# BBB_Connections.net
KiCad netlist of a schematic drawn in Altium Designer
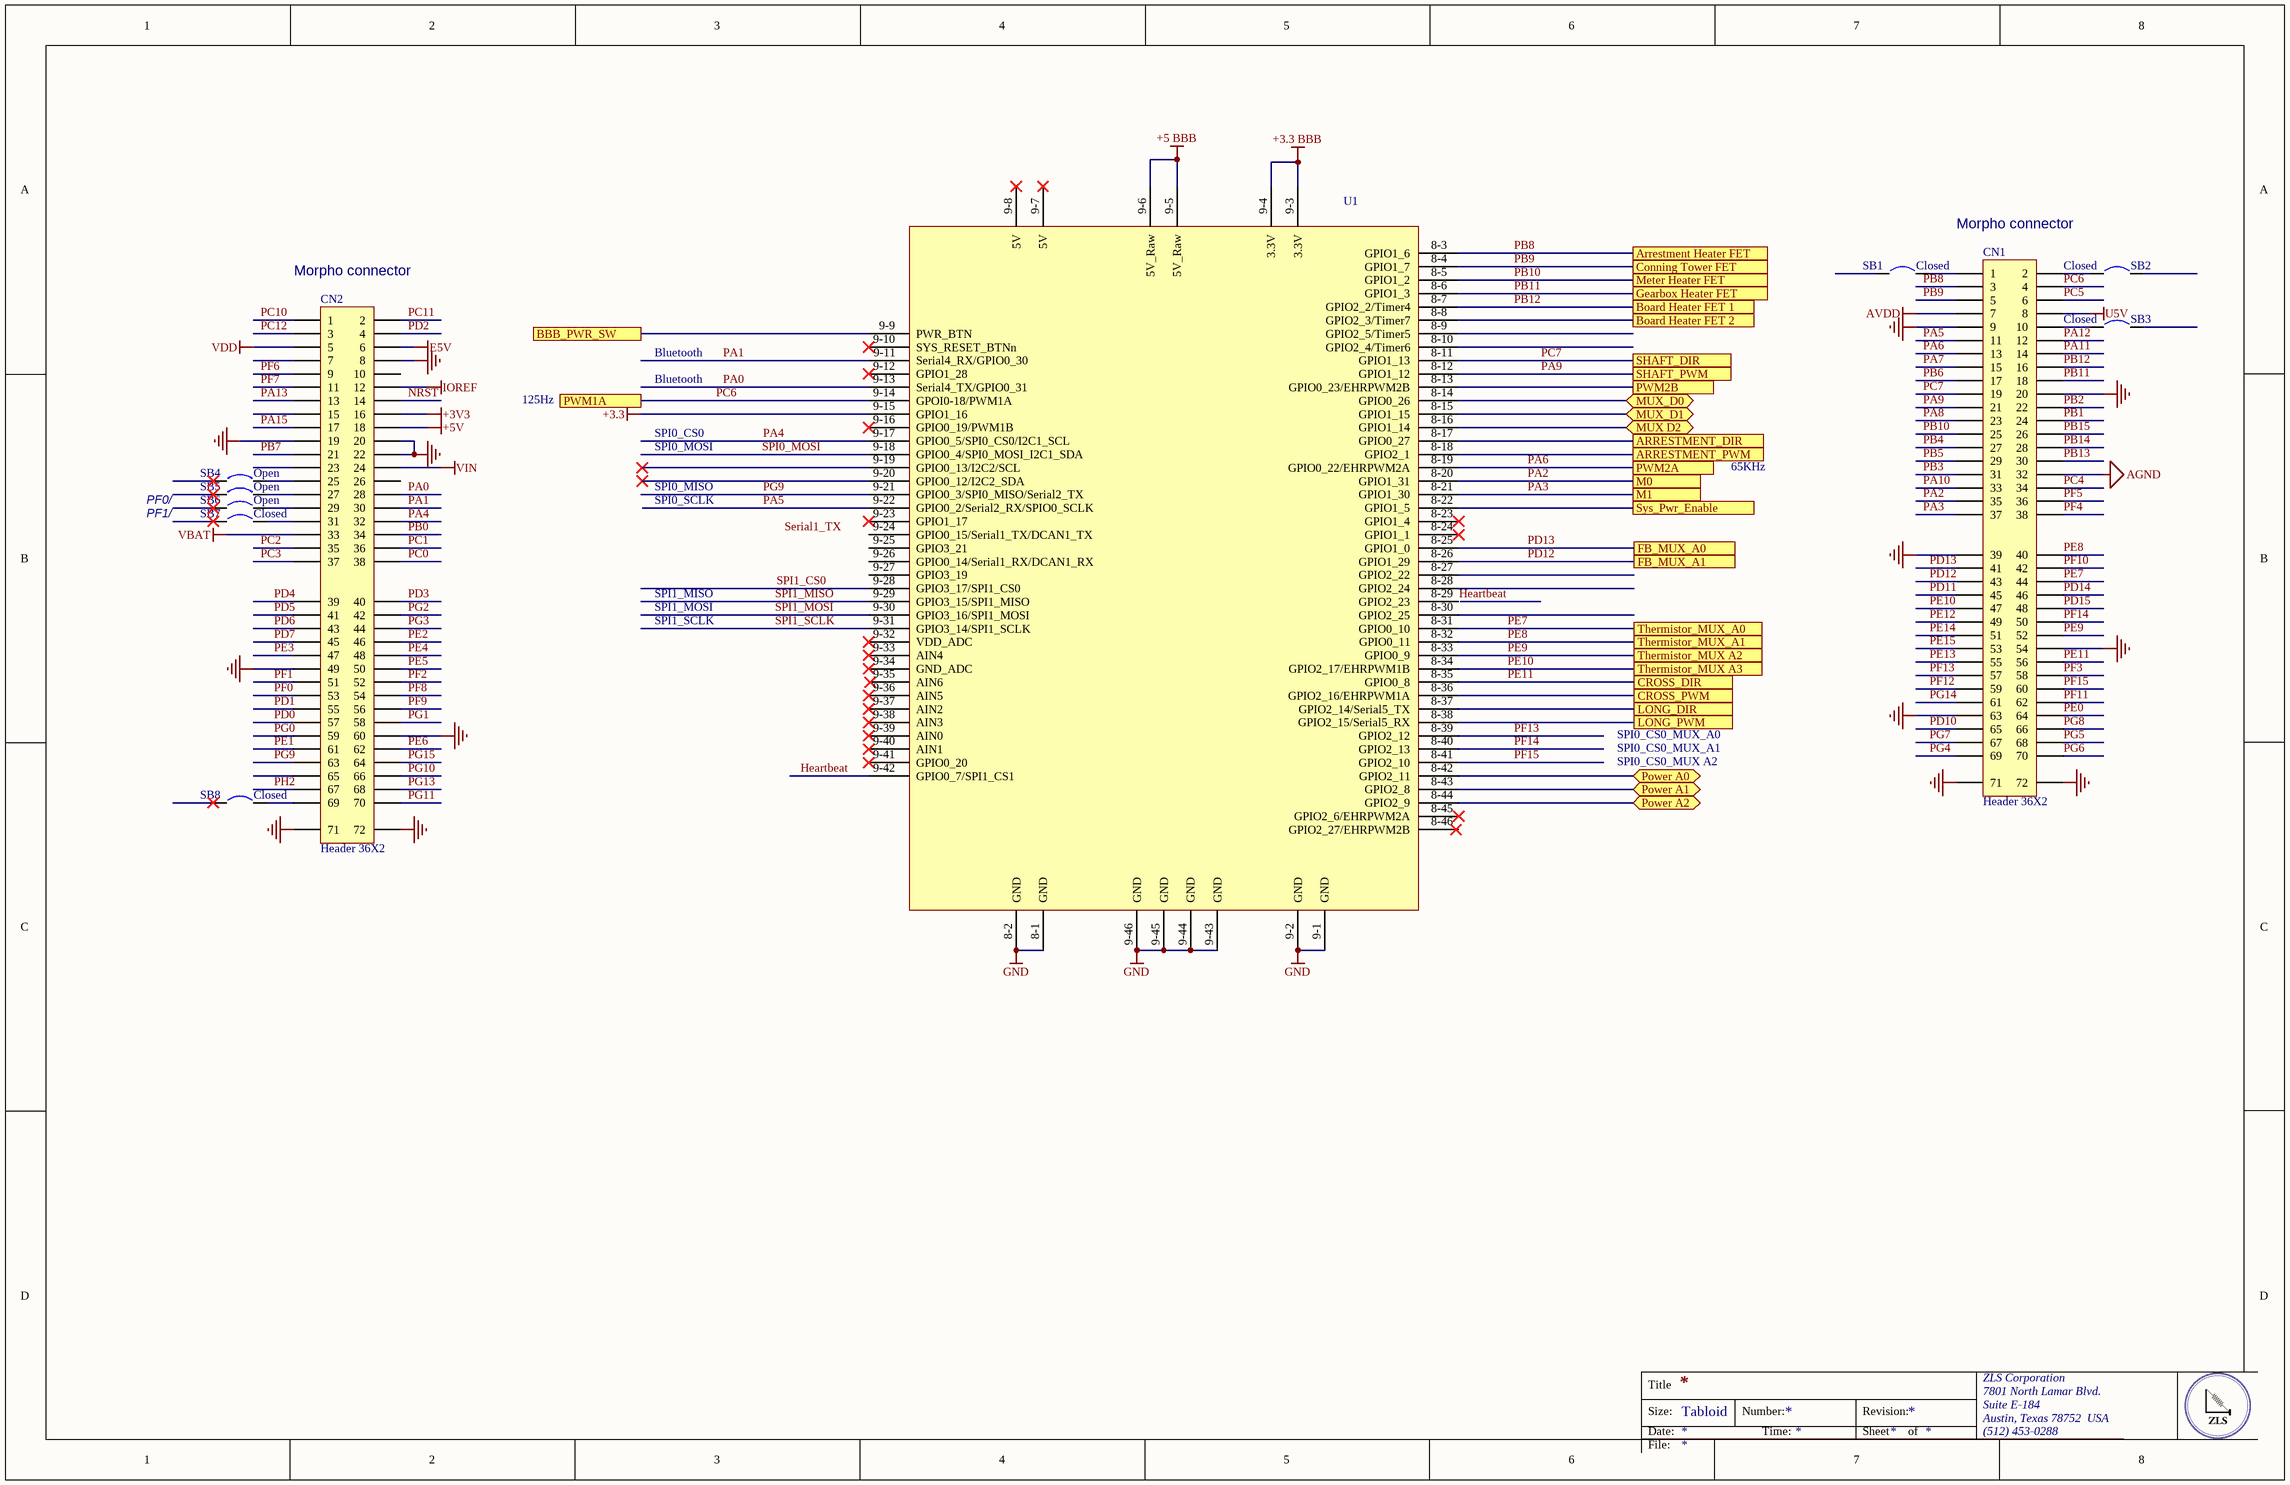
[diagram p0: BBB_Connections.SchDoc]

(export (version "E")
  (design (tool "Eeschema 10.0.6"))
  (components
    (comp (ref "CN1")
      (value "Header 36X2")
      (footprint "HDR_2x36_2R54_V_M")
      (description "Header, 36-Pin, Dual row")
      (fields (field (name "PUBLISHER") "Altium Limited"))
      (libsource (lib "MB1137") (part "Header 36X2"))
    )
    (comp (ref "CN2")
      (value "Header 36X2")
      (footprint "HDR_2x36_2R54_V_M")
      (description "Header, 36-Pin, Dual row")
      (fields (field (name "PUBLISHER") "Altium Limited"))
      (libsource (lib "MB1137") (part "Header 36X2"))
    )
    (comp (ref "SB1")
      (value "Closed")
      (footprint "SB_0603")
      (description "Circuit Breaker")
      (fields (field (name "PUBLISHER") "Altium Limited"))
      (libsource (lib "MB1167") (part "Circuit Breaker_close"))
    )
    (comp (ref "SB2")
      (value "Closed")
      (footprint "SB_0603")
      (description "Circuit Breaker")
      (fields (field (name "PUBLISHER") "Altium Limited"))
      (libsource (lib "") (part "Circuit Breaker_close_1"))
    )
    (comp (ref "SB3")
      (value "Closed")
      (footprint "SB_0603")
      (description "Circuit Breaker")
      (fields (field (name "PUBLISHER") "Altium Limited"))
      (libsource (lib "MB1167") (part "Circuit Breaker_close"))
    )
    (comp (ref "SB4")
      (value "Open")
      (footprint "SB_0603")
      (description "Circuit Breaker")
      (fields (field (name "PUBLISHER") "Altium Limited"))
      (libsource (lib "MB1167") (part "Circuit Breaker"))
    )
    (comp (ref "SB5")
      (value "Open")
      (footprint "SB_0603")
      (description "Circuit Breaker")
      (fields (field (name "PUBLISHER") "Altium Limited"))
      (libsource (lib "MB1167") (part "Circuit Breaker"))
    )
    (comp (ref "SB6")
      (value "Open")
      (footprint "SB_0603")
      (description "Circuit Breaker")
      (fields (field (name "PUBLISHER") "Altium Limited"))
      (libsource (lib "MB1167") (part "Circuit Breaker"))
    )
    (comp (ref "SB7")
      (value "Closed")
      (footprint "SB_0603")
      (description "Circuit Breaker")
      (fields (field (name "PUBLISHER") "Altium Limited"))
      (libsource (lib "MB1167") (part "Circuit Breaker_close"))
    )
    (comp (ref "SB8")
      (value "Closed")
      (footprint "SB_0603")
      (description "Circuit Breaker")
      (fields (field (name "PUBLISHER") "Altium Limited"))
      (libsource (lib "MB1167") (part "Circuit Breaker_close"))
    )
    (comp (ref "U1")
      (value "BBB Header x 2")
      (footprint "Beaglebone Black Thru")
      (description "Beaglebone Black Header")
      (fields
        (field (name "MANUFACTURER") "Samtec Inc.")
        (field (name "MANUFACTURER PART NUMBER") "SSW-123-03-G-D")
      )
      (libsource (lib "ZLS_Schematic_lib") (part "Beaglebone_Black"))
    )
  )
  (nets
    (net (code "1") (name "+3.3") (class "Default")
      (node (ref "U1") (pin "9-15") (pinfunction "GPIO1_16_9-15") (pintype "passive"))
    )
    (net (code "2") (name "+3.3 BBB") (class "Default")
      (node (ref "U1") (pin "9-3") (pinfunction "3.3V_9-3") (pintype "passive"))
      (node (ref "U1") (pin "9-4") (pinfunction "3.3V_9-4") (pintype "passive"))
    )
    (net (code "3") (name "+3V3") (class "Default")
      (node (ref "CN2") (pin "16") (pinfunction "16_16") (pintype "passive"))
    )
    (net (code "4") (name "+5 BBB") (class "Default")
      (node (ref "U1") (pin "9-5") (pinfunction "5V_Raw_9-5") (pintype "passive"))
      (node (ref "U1") (pin "9-6") (pinfunction "5V_Raw_9-6") (pintype "passive"))
    )
    (net (code "5") (name "+5V") (class "Default")
      (node (ref "CN2") (pin "18") (pinfunction "18_18") (pintype "passive"))
    )
    (net (code "6") (name "/ARRESTMENT_DIR") (class "Default")
      (node (ref "U1") (pin "8-17") (pinfunction "GPIO0_27_8-17") (pintype "passive"))
    )
    (net (code "7") (name "/ARRESTMENT_PWM") (class "Default")
      (node (ref "U1") (pin "8-18") (pinfunction "GPIO2_1_8-18") (pintype "passive"))
    )
    (net (code "8") (name "/BBB_PWR_SW") (class "Default")
      (node (ref "U1") (pin "9-9") (pinfunction "PWR_BTN_9-9") (pintype "passive"))
    )
    (net (code "9") (name "/Board Heater FET 2") (class "Default")
      (node (ref "U1") (pin "8-8") (pinfunction "GPIO2_3/Timer7_8-8") (pintype "passive"))
    )
    (net (code "10") (name "/CROSS_PWM") (class "Default")
      (node (ref "U1") (pin "8-36") (pinfunction "GPIO2_16/EHRPWM1A_8-36") (pintype "passive"))
    )
    (net (code "11") (name "/Heartbeat") (class "Default")
      (node (ref "U1") (pin "8-29") (pinfunction "GPIO2_23_8-29") (pintype "passive"))
      (node (ref "U1") (pin "9-42") (pinfunction "GPIO0_7/SPI1_CS1_9-42") (pintype "passive"))
    )
    (net (code "12") (name "/LONG_DIR") (class "Default")
      (node (ref "U1") (pin "8-37") (pinfunction "GPIO2_14/Serial5_TX_8-37") (pintype "passive"))
    )
    (net (code "13") (name "/LONG_PWM") (class "Default")
      (node (ref "U1") (pin "8-38") (pinfunction "GPIO2_15/Serial5_RX_8-38") (pintype "passive"))
    )
    (net (code "14") (name "/MUX D2") (class "Default")
      (node (ref "U1") (pin "8-16") (pinfunction "GPIO1_14_8-16") (pintype "passive"))
    )
    (net (code "15") (name "/MUX_D0") (class "Default")
      (node (ref "U1") (pin "8-14") (pinfunction "GPIO0_26_8-14") (pintype "passive"))
    )
    (net (code "16") (name "/MUX_D1") (class "Default")
      (node (ref "U1") (pin "8-15") (pinfunction "GPIO1_15_8-15") (pintype "passive"))
    )
    (net (code "17") (name "/NRST") (class "Default")
      (node (ref "CN2") (pin "14") (pinfunction "14_14") (pintype "passive"))
    )
    (net (code "18") (name "/PA0") (class "Default")
      (node (ref "CN2") (pin "28") (pinfunction "28_28") (pintype "passive"))
      (node (ref "U1") (pin "9-13") (pinfunction "Serial4_TX/GPIO0_31_9-13") (pintype "passive"))
    )
    (net (code "19") (name "/PA1") (class "Default")
      (node (ref "CN2") (pin "30") (pinfunction "30_30") (pintype "passive"))
      (node (ref "U1") (pin "9-11") (pinfunction "Serial4_RX/GPIO0_30_9-11") (pintype "passive"))
    )
    (net (code "20") (name "/PA2") (class "Default")
      (node (ref "CN1") (pin "35") (pinfunction "35_35") (pintype "passive"))
      (node (ref "U1") (pin "8-20") (pinfunction "GPIO1_31_8-20") (pintype "passive"))
    )
    (net (code "21") (name "/PA3") (class "Default")
      (node (ref "CN1") (pin "37") (pinfunction "37_37") (pintype "passive"))
      (node (ref "U1") (pin "8-21") (pinfunction "GPIO1_30_8-21") (pintype "passive"))
    )
    (net (code "22") (name "/PA4") (class "Default")
      (node (ref "CN2") (pin "32") (pinfunction "32_32") (pintype "passive"))
      (node (ref "U1") (pin "9-17") (pinfunction "GPIO0_5/SPI0_CS0/I2C1_SCL_9-17") (pintype "passive"))
    )
    (net (code "23") (name "/PA5") (class "Default")
      (node (ref "CN1") (pin "11") (pinfunction "11_11") (pintype "passive"))
      (node (ref "U1") (pin "9-22") (pinfunction "GPIO0_2/Serial2_RX/SPIO0_SCLK_9-22") (pintype "passive"))
    )
    (net (code "24") (name "/PA6") (class "Default")
      (node (ref "CN1") (pin "13") (pinfunction "13_13") (pintype "passive"))
      (node (ref "U1") (pin "8-19") (pinfunction "GPIO0_22/EHRPWM2A_8-19") (pintype "passive"))
    )
    (net (code "25") (name "/PA7") (class "Default")
      (node (ref "CN1") (pin "15") (pinfunction "15_15") (pintype "passive"))
    )
    (net (code "26") (name "/PA8") (class "Default")
      (node (ref "CN1") (pin "23") (pinfunction "23_23") (pintype "passive"))
    )
    (net (code "27") (name "/PA9") (class "Default")
      (node (ref "CN1") (pin "21") (pinfunction "21_21") (pintype "passive"))
      (node (ref "U1") (pin "8-12") (pinfunction "GPIO1_12_8-12") (pintype "passive"))
    )
    (net (code "28") (name "/PA10") (class "Default")
      (node (ref "CN1") (pin "33") (pinfunction "33_33") (pintype "passive"))
    )
    (net (code "29") (name "/PA11") (class "Default")
      (node (ref "CN1") (pin "14") (pinfunction "14_14") (pintype "passive"))
    )
    (net (code "30") (name "/PA12") (class "Default")
      (node (ref "CN1") (pin "12") (pinfunction "12_12") (pintype "passive"))
    )
    (net (code "31") (name "/PA13") (class "Default")
      (node (ref "CN2") (pin "13") (pinfunction "13_13") (pintype "passive"))
    )
    (net (code "32") (name "/PA15") (class "Default")
      (node (ref "CN2") (pin "17") (pinfunction "17_17") (pintype "passive"))
    )
    (net (code "33") (name "/PB0") (class "Default")
      (node (ref "CN2") (pin "34") (pinfunction "34_34") (pintype "passive"))
    )
    (net (code "34") (name "/PB1") (class "Default")
      (node (ref "CN1") (pin "24") (pinfunction "24_24") (pintype "passive"))
    )
    (net (code "35") (name "/PB2") (class "Default")
      (node (ref "CN1") (pin "22") (pinfunction "22_22") (pintype "passive"))
    )
    (net (code "36") (name "/PB3") (class "Default")
      (node (ref "CN1") (pin "31") (pinfunction "31_31") (pintype "passive"))
    )
    (net (code "37") (name "/PB4") (class "Default")
      (node (ref "CN1") (pin "27") (pinfunction "27_27") (pintype "passive"))
    )
    (net (code "38") (name "/PB5") (class "Default")
      (node (ref "CN1") (pin "29") (pinfunction "29_29") (pintype "passive"))
    )
    (net (code "39") (name "/PB6") (class "Default")
      (node (ref "CN1") (pin "17") (pinfunction "17_17") (pintype "passive"))
    )
    (net (code "40") (name "/PB7") (class "Default")
      (node (ref "CN2") (pin "21") (pinfunction "21_21") (pintype "passive"))
    )
    (net (code "41") (name "/PB8") (class "Default")
      (node (ref "CN1") (pin "3") (pinfunction "3_3") (pintype "passive"))
      (node (ref "U1") (pin "8-3") (pinfunction "GPIO1_6_8-3") (pintype "passive"))
    )
    (net (code "42") (name "/PB9") (class "Default")
      (node (ref "CN1") (pin "5") (pinfunction "5_5") (pintype "passive"))
      (node (ref "U1") (pin "8-4") (pinfunction "GPIO1_7_8-4") (pintype "passive"))
    )
    (net (code "43") (name "/PB10") (class "Default")
      (node (ref "CN1") (pin "25") (pinfunction "25_25") (pintype "passive"))
      (node (ref "U1") (pin "8-5") (pinfunction "GPIO1_2_8-5") (pintype "passive"))
    )
    (net (code "44") (name "/PB11") (class "Default")
      (node (ref "CN1") (pin "18") (pinfunction "18_18") (pintype "passive"))
      (node (ref "U1") (pin "8-6") (pinfunction "GPIO1_3_8-6") (pintype "passive"))
    )
    (net (code "45") (name "/PB12") (class "Default")
      (node (ref "CN1") (pin "16") (pinfunction "16_16") (pintype "passive"))
      (node (ref "U1") (pin "8-7") (pinfunction "GPIO2_2/Timer4_8-7") (pintype "passive"))
    )
    (net (code "46") (name "/PB13") (class "Default")
      (node (ref "CN1") (pin "30") (pinfunction "30_30") (pintype "passive"))
    )
    (net (code "47") (name "/PB14") (class "Default")
      (node (ref "CN1") (pin "28") (pinfunction "28_28") (pintype "passive"))
    )
    (net (code "48") (name "/PB15") (class "Default")
      (node (ref "CN1") (pin "26") (pinfunction "26_26") (pintype "passive"))
    )
    (net (code "49") (name "/PC0") (class "Default")
      (node (ref "CN2") (pin "38") (pinfunction "38_38") (pintype "passive"))
    )
    (net (code "50") (name "/PC1") (class "Default")
      (node (ref "CN2") (pin "36") (pinfunction "36_36") (pintype "passive"))
    )
    (net (code "51") (name "/PC2") (class "Default")
      (node (ref "CN2") (pin "35") (pinfunction "35_35") (pintype "passive"))
    )
    (net (code "52") (name "/PC3") (class "Default")
      (node (ref "CN2") (pin "37") (pinfunction "37_37") (pintype "passive"))
    )
    (net (code "53") (name "/PC4") (class "Default")
      (node (ref "CN1") (pin "34") (pinfunction "34_34") (pintype "passive"))
    )
    (net (code "54") (name "/PC5") (class "Default")
      (node (ref "CN1") (pin "6") (pinfunction "6_6") (pintype "passive"))
    )
    (net (code "55") (name "/PC6") (class "Default")
      (node (ref "CN1") (pin "4") (pinfunction "4_4") (pintype "passive"))
      (node (ref "U1") (pin "9-14") (pinfunction "GPOI0-18/PWM1A_9-14") (pintype "passive"))
    )
    (net (code "56") (name "/PC7") (class "Default")
      (node (ref "CN1") (pin "19") (pinfunction "19_19") (pintype "passive"))
      (node (ref "U1") (pin "8-11") (pinfunction "GPIO1_13_8-11") (pintype "passive"))
    )
    (net (code "57") (name "/PC10") (class "Default")
      (node (ref "CN2") (pin "1") (pinfunction "1_1") (pintype "passive"))
    )
    (net (code "58") (name "/PC11") (class "Default")
      (node (ref "CN2") (pin "2") (pinfunction "2_2") (pintype "passive"))
    )
    (net (code "59") (name "/PC12") (class "Default")
      (node (ref "CN2") (pin "3") (pinfunction "3_3") (pintype "passive"))
    )
    (net (code "60") (name "/PD0") (class "Default")
      (node (ref "CN2") (pin "57") (pinfunction "57_57") (pintype "passive"))
    )
    (net (code "61") (name "/PD1") (class "Default")
      (node (ref "CN2") (pin "55") (pinfunction "55_55") (pintype "passive"))
    )
    (net (code "62") (name "/PD2") (class "Default")
      (node (ref "CN2") (pin "4") (pinfunction "4_4") (pintype "passive"))
    )
    (net (code "63") (name "/PD3") (class "Default")
      (node (ref "CN2") (pin "40") (pinfunction "40_40") (pintype "passive"))
    )
    (net (code "64") (name "/PD4") (class "Default")
      (node (ref "CN2") (pin "39") (pinfunction "39_39") (pintype "passive"))
    )
    (net (code "65") (name "/PD5") (class "Default")
      (node (ref "CN2") (pin "41") (pinfunction "41_41") (pintype "passive"))
    )
    (net (code "66") (name "/PD6") (class "Default")
      (node (ref "CN2") (pin "43") (pinfunction "43_43") (pintype "passive"))
    )
    (net (code "67") (name "/PD7") (class "Default")
      (node (ref "CN2") (pin "45") (pinfunction "45_45") (pintype "passive"))
    )
    (net (code "68") (name "/PD10") (class "Default")
      (node (ref "CN1") (pin "65") (pinfunction "65_65") (pintype "passive"))
    )
    (net (code "69") (name "/PD11") (class "Default")
      (node (ref "CN1") (pin "45") (pinfunction "45_45") (pintype "passive"))
    )
    (net (code "70") (name "/PD12") (class "Default")
      (node (ref "CN1") (pin "43") (pinfunction "43_43") (pintype "passive"))
      (node (ref "U1") (pin "8-26") (pinfunction "GPIO1_29_8-26") (pintype "passive"))
    )
    (net (code "71") (name "/PD13") (class "Default")
      (node (ref "CN1") (pin "41") (pinfunction "41_41") (pintype "passive"))
      (node (ref "U1") (pin "8-25") (pinfunction "GPIO1_0_8-25") (pintype "passive"))
    )
    (net (code "72") (name "/PD14") (class "Default")
      (node (ref "CN1") (pin "46") (pinfunction "46_46") (pintype "passive"))
    )
    (net (code "73") (name "/PD15") (class "Default")
      (node (ref "CN1") (pin "48") (pinfunction "48_48") (pintype "passive"))
    )
    (net (code "74") (name "/PE0") (class "Default")
      (node (ref "CN1") (pin "64") (pinfunction "64_64") (pintype "passive"))
    )
    (net (code "75") (name "/PE1") (class "Default")
      (node (ref "CN2") (pin "61") (pinfunction "61_61") (pintype "passive"))
    )
    (net (code "76") (name "/PE2") (class "Default")
      (node (ref "CN2") (pin "46") (pinfunction "46_46") (pintype "passive"))
    )
    (net (code "77") (name "/PE3") (class "Default")
      (node (ref "CN2") (pin "47") (pinfunction "47_47") (pintype "passive"))
    )
    (net (code "78") (name "/PE4") (class "Default")
      (node (ref "CN2") (pin "48") (pinfunction "48_48") (pintype "passive"))
    )
    (net (code "79") (name "/PE5") (class "Default")
      (node (ref "CN2") (pin "50") (pinfunction "50_50") (pintype "passive"))
    )
    (net (code "80") (name "/PE6") (class "Default")
      (node (ref "CN2") (pin "62") (pinfunction "62_62") (pintype "passive"))
    )
    (net (code "81") (name "/PE7") (class "Default")
      (node (ref "CN1") (pin "44") (pinfunction "44_44") (pintype "passive"))
      (node (ref "U1") (pin "8-31") (pinfunction "GPIO0_10_8-31") (pintype "passive"))
    )
    (net (code "82") (name "/PE8") (class "Default")
      (node (ref "CN1") (pin "40") (pinfunction "40_40") (pintype "passive"))
      (node (ref "U1") (pin "8-32") (pinfunction "GPIO0_11_8-32") (pintype "passive"))
    )
    (net (code "83") (name "/PE9") (class "Default")
      (node (ref "CN1") (pin "52") (pinfunction "52_52") (pintype "passive"))
      (node (ref "U1") (pin "8-33") (pinfunction "GPIO0_9_8-33") (pintype "passive"))
    )
    (net (code "84") (name "/PE10") (class "Default")
      (node (ref "CN1") (pin "47") (pinfunction "47_47") (pintype "passive"))
      (node (ref "U1") (pin "8-34") (pinfunction "GPIO2_17/EHRPWM1B_8-34") (pintype "passive"))
    )
    (net (code "85") (name "/PE11") (class "Default")
      (node (ref "CN1") (pin "56") (pinfunction "56_56") (pintype "passive"))
      (node (ref "U1") (pin "8-35") (pinfunction "GPIO0_8_8-35") (pintype "passive"))
    )
    (net (code "86") (name "/PE12") (class "Default")
      (node (ref "CN1") (pin "49") (pinfunction "49_49") (pintype "passive"))
    )
    (net (code "87") (name "/PE13") (class "Default")
      (node (ref "CN1") (pin "55") (pinfunction "55_55") (pintype "passive"))
    )
    (net (code "88") (name "/PE14") (class "Default")
      (node (ref "CN1") (pin "51") (pinfunction "51_51") (pintype "passive"))
    )
    (net (code "89") (name "/PE15") (class "Default")
      (node (ref "CN1") (pin "53") (pinfunction "53_53") (pintype "passive"))
    )
    (net (code "90") (name "/PF0") (class "Default")
      (node (ref "CN2") (pin "53") (pinfunction "53_53") (pintype "passive"))
    )
    (net (code "91") (name "/PF1") (class "Default")
      (node (ref "CN2") (pin "51") (pinfunction "51_51") (pintype "passive"))
    )
    (net (code "92") (name "/PF2") (class "Default")
      (node (ref "CN2") (pin "52") (pinfunction "52_52") (pintype "passive"))
    )
    (net (code "93") (name "/PF3") (class "Default")
      (node (ref "CN1") (pin "58") (pinfunction "58_58") (pintype "passive"))
    )
    (net (code "94") (name "/PF4") (class "Default")
      (node (ref "CN1") (pin "38") (pinfunction "38_38") (pintype "passive"))
    )
    (net (code "95") (name "/PF5") (class "Default")
      (node (ref "CN1") (pin "36") (pinfunction "36_36") (pintype "passive"))
    )
    (net (code "96") (name "/PF6") (class "Default")
      (node (ref "CN2") (pin "9") (pinfunction "9_9") (pintype "passive"))
    )
    (net (code "97") (name "/PF7") (class "Default")
      (node (ref "CN2") (pin "11") (pinfunction "11_11") (pintype "passive"))
    )
    (net (code "98") (name "/PF8") (class "Default")
      (node (ref "CN2") (pin "54") (pinfunction "54_54") (pintype "passive"))
    )
    (net (code "99") (name "/PF9") (class "Default")
      (node (ref "CN2") (pin "56") (pinfunction "56_56") (pintype "passive"))
    )
    (net (code "100") (name "/PF10") (class "Default")
      (node (ref "CN1") (pin "42") (pinfunction "42_42") (pintype "passive"))
    )
    (net (code "101") (name "/PF11") (class "Default")
      (node (ref "CN1") (pin "62") (pinfunction "62_62") (pintype "passive"))
    )
    (net (code "102") (name "/PF12") (class "Default")
      (node (ref "CN1") (pin "59") (pinfunction "59_59") (pintype "passive"))
    )
    (net (code "103") (name "/PF13") (class "Default")
      (node (ref "CN1") (pin "57") (pinfunction "57_57") (pintype "passive"))
      (node (ref "U1") (pin "8-39") (pinfunction "GPIO2_12_8-39") (pintype "passive"))
    )
    (net (code "104") (name "/PF14") (class "Default")
      (node (ref "CN1") (pin "50") (pinfunction "50_50") (pintype "passive"))
      (node (ref "U1") (pin "8-40") (pinfunction "GPIO2_13_8-40") (pintype "passive"))
    )
    (net (code "105") (name "/PF15") (class "Default")
      (node (ref "CN1") (pin "60") (pinfunction "60_60") (pintype "passive"))
      (node (ref "U1") (pin "8-41") (pinfunction "GPIO2_10_8-41") (pintype "passive"))
    )
    (net (code "106") (name "/PG0") (class "Default")
      (node (ref "CN2") (pin "59") (pinfunction "59_59") (pintype "passive"))
    )
    (net (code "107") (name "/PG1") (class "Default")
      (node (ref "CN2") (pin "58") (pinfunction "58_58") (pintype "passive"))
    )
    (net (code "108") (name "/PG2") (class "Default")
      (node (ref "CN2") (pin "42") (pinfunction "42_42") (pintype "passive"))
    )
    (net (code "109") (name "/PG3") (class "Default")
      (node (ref "CN2") (pin "44") (pinfunction "44_44") (pintype "passive"))
    )
    (net (code "110") (name "/PG4") (class "Default")
      (node (ref "CN1") (pin "69") (pinfunction "69_69") (pintype "passive"))
    )
    (net (code "111") (name "/PG5") (class "Default")
      (node (ref "CN1") (pin "68") (pinfunction "68_68") (pintype "passive"))
    )
    (net (code "112") (name "/PG6") (class "Default")
      (node (ref "CN1") (pin "70") (pinfunction "70_70") (pintype "passive"))
    )
    (net (code "113") (name "/PG7") (class "Default")
      (node (ref "CN1") (pin "67") (pinfunction "67_67") (pintype "passive"))
    )
    (net (code "114") (name "/PG8") (class "Default")
      (node (ref "CN1") (pin "66") (pinfunction "66_66") (pintype "passive"))
    )
    (net (code "115") (name "/PG9") (class "Default")
      (node (ref "CN2") (pin "63") (pinfunction "63_63") (pintype "passive"))
      (node (ref "U1") (pin "9-21") (pinfunction "GPIO0_3/SPI0_MISO/Serial2_TX_9-21") (pintype "passive"))
    )
    (net (code "116") (name "/PG10") (class "Default")
      (node (ref "CN2") (pin "66") (pinfunction "66_66") (pintype "passive"))
    )
    (net (code "117") (name "/PG11") (class "Default")
      (node (ref "CN2") (pin "70") (pinfunction "70_70") (pintype "passive"))
    )
    (net (code "118") (name "/PG13") (class "Default")
      (node (ref "CN2") (pin "68") (pinfunction "68_68") (pintype "passive"))
    )
    (net (code "119") (name "/PG14") (class "Default")
      (node (ref "CN1") (pin "61") (pinfunction "61_61") (pintype "passive"))
    )
    (net (code "120") (name "/PG15") (class "Default")
      (node (ref "CN2") (pin "64") (pinfunction "64_64") (pintype "passive"))
    )
    (net (code "121") (name "/PH2") (class "Default")
      (node (ref "CN2") (pin "67") (pinfunction "67_67") (pintype "passive"))
    )
    (net (code "122") (name "/PWM2B") (class "Default")
      (node (ref "U1") (pin "8-13") (pinfunction "GPIO0_23/EHRPWM2B_8-13") (pintype "passive"))
    )
    (net (code "123") (name "/Power A0") (class "Default")
      (node (ref "U1") (pin "8-42") (pinfunction "GPIO2_11_8-42") (pintype "passive"))
    )
    (net (code "124") (name "/Power A1") (class "Default")
      (node (ref "U1") (pin "8-43") (pinfunction "GPIO2_8_8-43") (pintype "passive"))
    )
    (net (code "125") (name "/Power A2") (class "Default")
      (node (ref "U1") (pin "8-44") (pinfunction "GPIO2_9_8-44") (pintype "passive"))
    )
    (net (code "126") (name "/SPI0_MOSI") (class "Default")
      (node (ref "U1") (pin "9-18") (pinfunction "GPIO0_4/SPI0_MOSI_I2C1_SDA_9-18") (pintype "passive"))
    )
    (net (code "127") (name "/SPI1_CS0") (class "Default")
      (node (ref "U1") (pin "9-28") (pinfunction "GPIO3_17/SPI1_CS0_9-28") (pintype "passive"))
    )
    (net (code "128") (name "/SPI1_MISO") (class "Default")
      (node (ref "U1") (pin "9-29") (pinfunction "GPIO3_15/SPI1_MISO_9-29") (pintype "passive"))
    )
    (net (code "129") (name "/SPI1_MOSI") (class "Default")
      (node (ref "U1") (pin "9-30") (pinfunction "GPIO3_16/SPI1_MOSI_9-30") (pintype "passive"))
    )
    (net (code "130") (name "/SPI1_SCLK") (class "Default")
      (node (ref "U1") (pin "9-31") (pinfunction "GPIO3_14/SPI1_SCLK_9-31") (pintype "passive"))
    )
    (net (code "132") (name "/Sys_Pwr_Enable") (class "Default")
      (node (ref "U1") (pin "8-22") (pinfunction "GPIO1_5_8-22") (pintype "passive"))
    )
    (net (code "133") (name "AGND") (class "Default")
      (node (ref "CN1") (pin "32") (pinfunction "32_32") (pintype "passive"))
    )
    (net (code "134") (name "AVDD") (class "Default")
      (node (ref "CN1") (pin "7") (pinfunction "7_7") (pintype "passive"))
    )
    (net (code "135") (name "E5V") (class "Default")
      (node (ref "CN2") (pin "6") (pinfunction "6_6") (pintype "passive"))
    )
    (net (code "136") (name "GND") (class "Default")
      (node (ref "CN1") (pin "20") (pinfunction "20_20") (pintype "passive"))
      (node (ref "CN1") (pin "39") (pinfunction "39_39") (pintype "passive"))
      (node (ref "CN1") (pin "54") (pinfunction "54_54") (pintype "passive"))
      (node (ref "CN1") (pin "63") (pinfunction "63_63") (pintype "passive"))
      (node (ref "CN1") (pin "71") (pinfunction "71_71") (pintype "passive"))
      (node (ref "CN1") (pin "72") (pinfunction "72_72") (pintype "passive"))
      (node (ref "CN1") (pin "9") (pinfunction "9_9") (pintype "passive"))
      (node (ref "CN2") (pin "19") (pinfunction "19_19") (pintype "passive"))
      (node (ref "CN2") (pin "20") (pinfunction "20_20") (pintype "passive"))
      (node (ref "CN2") (pin "22") (pinfunction "22_22") (pintype "passive"))
      (node (ref "CN2") (pin "49") (pinfunction "49_49") (pintype "passive"))
      (node (ref "CN2") (pin "60") (pinfunction "60_60") (pintype "passive"))
      (node (ref "CN2") (pin "71") (pinfunction "71_71") (pintype "passive"))
      (node (ref "CN2") (pin "72") (pinfunction "72_72") (pintype "passive"))
      (node (ref "CN2") (pin "8") (pinfunction "8_8") (pintype "passive"))
      (node (ref "U1") (pin "8-1") (pinfunction "GND_8-1") (pintype "passive"))
      (node (ref "U1") (pin "8-2") (pinfunction "GND_8-2") (pintype "passive"))
      (node (ref "U1") (pin "9-1") (pinfunction "GND_9-1") (pintype "passive"))
      (node (ref "U1") (pin "9-2") (pinfunction "GND_9-2") (pintype "passive"))
      (node (ref "U1") (pin "9-43") (pinfunction "GND_9-43") (pintype "passive"))
      (node (ref "U1") (pin "9-44") (pinfunction "GND_9-44") (pintype "passive"))
      (node (ref "U1") (pin "9-45") (pinfunction "GND_9-45") (pintype "passive"))
      (node (ref "U1") (pin "9-46") (pinfunction "GND_9-46") (pintype "passive"))
    )
    (net (code "137") (name "IOREF") (class "Default")
      (node (ref "CN2") (pin "12") (pinfunction "12_12") (pintype "passive"))
    )
    (net (code "138") (name "Net-(CN1-Pad1)") (class "Default")
      (node (ref "CN1") (pin "1") (pinfunction "1_1") (pintype "passive"))
      (node (ref "SB1") (pin "2") (pinfunction "2_2") (pintype "passive"))
    )
    (net (code "139") (name "Net-(CN1-Pad2)") (class "Default")
      (node (ref "CN1") (pin "2") (pinfunction "2_2") (pintype "passive"))
      (node (ref "SB2") (pin "2") (pinfunction "2_2") (pintype "passive"))
    )
    (net (code "140") (name "Net-(CN1-Pad10)") (class "Default")
      (node (ref "CN1") (pin "10") (pinfunction "10_10") (pintype "passive"))
      (node (ref "SB3") (pin "1") (pinfunction "1_1") (pintype "passive"))
    )
    (net (code "141") (name "Net-(CN2-Pad25)") (class "Default")
      (node (ref "CN2") (pin "25") (pinfunction "25_25") (pintype "passive"))
      (node (ref "SB4") (pin "2") (pinfunction "2_2") (pintype "passive"))
    )
    (net (code "142") (name "Net-(CN2-Pad27)") (class "Default")
      (node (ref "CN2") (pin "27") (pinfunction "27_27") (pintype "passive"))
      (node (ref "SB5") (pin "2") (pinfunction "2_2") (pintype "passive"))
    )
    (net (code "143") (name "Net-(CN2-Pad29)") (class "Default")
      (node (ref "CN2") (pin "29") (pinfunction "29_29") (pintype "passive"))
      (node (ref "SB6") (pin "2") (pinfunction "2_2") (pintype "passive"))
    )
    (net (code "144") (name "Net-(CN2-Pad31)") (class "Default")
      (node (ref "CN2") (pin "31") (pinfunction "31_31") (pintype "passive"))
      (node (ref "SB7") (pin "2") (pinfunction "2_2") (pintype "passive"))
    )
    (net (code "145") (name "Net-(CN2-Pad69)") (class "Default")
      (node (ref "CN2") (pin "69") (pinfunction "69_69") (pintype "passive"))
      (node (ref "SB8") (pin "2") (pinfunction "2_2") (pintype "passive"))
    )
    (net (code "146") (name "U5V") (class "Default")
      (node (ref "CN1") (pin "8") (pinfunction "8_8") (pintype "passive"))
    )
    (net (code "147") (name "VBAT") (class "Default")
      (node (ref "CN2") (pin "33") (pinfunction "33_33") (pintype "passive"))
    )
    (net (code "148") (name "VDD") (class "Default")
      (node (ref "CN2") (pin "5") (pinfunction "5_5") (pintype "passive"))
    )
    (net (code "149") (name "VIN") (class "Default")
      (node (ref "CN2") (pin "24") (pinfunction "24_24") (pintype "passive"))
    )
    (net (code "150") (name "unconnected-(CN2-Pad7)") (class "Default")
      (node (ref "CN2") (pin "7") (pinfunction "7_7") (pintype "passive"))
    )
    (net (code "151") (name "unconnected-(CN2-Pad10)") (class "Default")
      (node (ref "CN2") (pin "10") (pinfunction "10_10") (pintype "passive"))
    )
    (net (code "152") (name "unconnected-(CN2-Pad15)") (class "Default")
      (node (ref "CN2") (pin "15") (pinfunction "15_15") (pintype "passive"))
    )
    (net (code "153") (name "unconnected-(CN2-Pad23)") (class "Default")
      (node (ref "CN2") (pin "23") (pinfunction "23_23") (pintype "passive"))
    )
    (net (code "154") (name "unconnected-(CN2-Pad26)") (class "Default")
      (node (ref "CN2") (pin "26") (pinfunction "26_26") (pintype "passive"))
    )
    (net (code "155") (name "unconnected-(CN2-Pad65)") (class "Default")
      (node (ref "CN2") (pin "65") (pinfunction "65_65") (pintype "passive"))
    )
    (net (code "156") (name "unconnected-(SB1-Pad1)") (class "Default")
      (node (ref "SB1") (pin "1") (pinfunction "1_1") (pintype "passive"))
    )
    (net (code "157") (name "unconnected-(SB2-Pad1)") (class "Default")
      (node (ref "SB2") (pin "1") (pinfunction "1_1") (pintype "passive"))
    )
    (net (code "158") (name "unconnected-(SB3-Pad2)") (class "Default")
      (node (ref "SB3") (pin "2") (pinfunction "2_2") (pintype "passive"))
    )
    (net (code "159") (name "unconnected-(SB4-Pad1)") (class "Default")
      (node (ref "SB4") (pin "1") (pinfunction "1_1") (pintype "passive+no_connect"))
    )
    (net (code "160") (name "unconnected-(SB5-Pad1)") (class "Default")
      (node (ref "SB5") (pin "1") (pinfunction "1_1") (pintype "passive+no_connect"))
    )
    (net (code "161") (name "unconnected-(SB6-Pad1)") (class "Default")
      (node (ref "SB6") (pin "1") (pinfunction "1_1") (pintype "passive+no_connect"))
    )
    (net (code "162") (name "unconnected-(SB7-Pad1)") (class "Default")
      (node (ref "SB7") (pin "1") (pinfunction "1_1") (pintype "passive+no_connect"))
    )
    (net (code "163") (name "unconnected-(SB8-Pad1)") (class "Default")
      (node (ref "SB8") (pin "1") (pinfunction "1_1") (pintype "passive+no_connect"))
    )
    (net (code "164") (name "unconnected-(U1-5V-Pad9-7)") (class "Default")
      (node (ref "U1") (pin "9-7") (pinfunction "5V_9-7") (pintype "passive+no_connect"))
    )
    (net (code "165") (name "unconnected-(U1-5V-Pad9-8)") (class "Default")
      (node (ref "U1") (pin "9-8") (pinfunction "5V_9-8") (pintype "passive+no_connect"))
    )
    (net (code "166") (name "unconnected-(U1-AIN0-Pad9-39)") (class "Default")
      (node (ref "U1") (pin "9-39") (pinfunction "AIN0_9-39") (pintype "passive+no_connect"))
    )
    (net (code "167") (name "unconnected-(U1-AIN1-Pad9-40)") (class "Default")
      (node (ref "U1") (pin "9-40") (pinfunction "AIN1_9-40") (pintype "passive+no_connect"))
    )
    (net (code "168") (name "unconnected-(U1-AIN2-Pad9-37)") (class "Default")
      (node (ref "U1") (pin "9-37") (pinfunction "AIN2_9-37") (pintype "passive+no_connect"))
    )
    (net (code "169") (name "unconnected-(U1-AIN3-Pad9-38)") (class "Default")
      (node (ref "U1") (pin "9-38") (pinfunction "AIN3_9-38") (pintype "passive+no_connect"))
    )
    (net (code "170") (name "unconnected-(U1-AIN4-Pad9-33)") (class "Default")
      (node (ref "U1") (pin "9-33") (pinfunction "AIN4_9-33") (pintype "passive+no_connect"))
    )
    (net (code "171") (name "unconnected-(U1-AIN5-Pad9-36)") (class "Default")
      (node (ref "U1") (pin "9-36") (pinfunction "AIN5_9-36") (pintype "passive+no_connect"))
    )
    (net (code "172") (name "unconnected-(U1-AIN6-Pad9-35)") (class "Default")
      (node (ref "U1") (pin "9-35") (pinfunction "AIN6_9-35") (pintype "passive"))
    )
    (net (code "173") (name "unconnected-(U1-GND_ADC-Pad9-34)") (class "Default")
      (node (ref "U1") (pin "9-34") (pinfunction "GND_ADC_9-34") (pintype "passive+no_connect"))
    )
    (net (code "174") (name "unconnected-(U1-GPIO0_12{slash}I2C2_SDA-Pad9-20)") (class "Default")
      (node (ref "U1") (pin "9-20") (pinfunction "GPIO0_12/I2C2_SDA_9-20") (pintype "passive+no_connect"))
    )
    (net (code "175") (name "unconnected-(U1-GPIO0_13{slash}I2C2{slash}SCL-Pad9-19)") (class "Default")
      (node (ref "U1") (pin "9-19") (pinfunction "GPIO0_13/I2C2/SCL_9-19") (pintype "passive+no_connect"))
    )
    (net (code "176") (name "unconnected-(U1-GPIO0_14{slash}Serial1_RX{slash}DCAN1_RX-Pad9-26)") (class "Default")
      (node (ref "U1") (pin "9-26") (pinfunction "GPIO0_14/Serial1_RX/DCAN1_RX_9-26") (pintype "passive"))
    )
    (net (code "177") (name "unconnected-(U1-GPIO0_15{slash}Serial1_TX{slash}DCAN1_TX-Pad9-24)") (class "Default")
      (node (ref "U1") (pin "9-24") (pinfunction "GPIO0_15/Serial1_TX/DCAN1_TX_9-24") (pintype "passive"))
    )
    (net (code "178") (name "unconnected-(U1-GPIO0_19{slash}PWM1B-Pad9-16)") (class "Default")
      (node (ref "U1") (pin "9-16") (pinfunction "GPIO0_19/PWM1B_9-16") (pintype "passive+no_connect"))
    )
    (net (code "179") (name "unconnected-(U1-GPIO0_20-Pad9-41)") (class "Default")
      (node (ref "U1") (pin "9-41") (pinfunction "GPIO0_20_9-41") (pintype "passive+no_connect"))
    )
    (net (code "180") (name "unconnected-(U1-GPIO1_1-Pad8-24)") (class "Default")
      (node (ref "U1") (pin "8-24") (pinfunction "GPIO1_1_8-24") (pintype "passive+no_connect"))
    )
    (net (code "181") (name "unconnected-(U1-GPIO1_4-Pad8-23)") (class "Default")
      (node (ref "U1") (pin "8-23") (pinfunction "GPIO1_4_8-23") (pintype "passive+no_connect"))
    )
    (net (code "182") (name "unconnected-(U1-GPIO1_17-Pad9-23)") (class "Default")
      (node (ref "U1") (pin "9-23") (pinfunction "GPIO1_17_9-23") (pintype "passive+no_connect"))
    )
    (net (code "183") (name "unconnected-(U1-GPIO1_28-Pad9-12)") (class "Default")
      (node (ref "U1") (pin "9-12") (pinfunction "GPIO1_28_9-12") (pintype "passive+no_connect"))
    )
    (net (code "184") (name "unconnected-(U1-GPIO2_4{slash}Timer6-Pad8-10)") (class "Default")
      (node (ref "U1") (pin "8-10") (pinfunction "GPIO2_4/Timer6_8-10") (pintype "passive"))
    )
    (net (code "185") (name "unconnected-(U1-GPIO2_5{slash}Timer5-Pad8-9)") (class "Default")
      (node (ref "U1") (pin "8-9") (pinfunction "GPIO2_5/Timer5_8-9") (pintype "passive"))
    )
    (net (code "186") (name "unconnected-(U1-GPIO2_6{slash}EHRPWM2A-Pad8-45)") (class "Default")
      (node (ref "U1") (pin "8-45") (pinfunction "GPIO2_6/EHRPWM2A_8-45") (pintype "passive+no_connect"))
    )
    (net (code "187") (name "unconnected-(U1-GPIO2_22-Pad8-27)") (class "Default")
      (node (ref "U1") (pin "8-27") (pinfunction "GPIO2_22_8-27") (pintype "passive"))
    )
    (net (code "188") (name "unconnected-(U1-GPIO2_24-Pad8-28)") (class "Default")
      (node (ref "U1") (pin "8-28") (pinfunction "GPIO2_24_8-28") (pintype "passive"))
    )
    (net (code "189") (name "unconnected-(U1-GPIO2_25-Pad8-30)") (class "Default")
      (node (ref "U1") (pin "8-30") (pinfunction "GPIO2_25_8-30") (pintype "passive"))
    )
    (net (code "190") (name "unconnected-(U1-GPIO2_27{slash}EHRPWM2B-Pad8-46)") (class "Default")
      (node (ref "U1") (pin "8-46") (pinfunction "GPIO2_27/EHRPWM2B_8-46") (pintype "passive"))
    )
    (net (code "191") (name "unconnected-(U1-GPIO3_19-Pad9-27)") (class "Default")
      (node (ref "U1") (pin "9-27") (pinfunction "GPIO3_19_9-27") (pintype "passive"))
    )
    (net (code "192") (name "unconnected-(U1-GPIO3_21-Pad9-25)") (class "Default")
      (node (ref "U1") (pin "9-25") (pinfunction "GPIO3_21_9-25") (pintype "passive"))
    )
    (net (code "193") (name "unconnected-(U1-SYS_RESET_BTNn-Pad9-10)") (class "Default")
      (node (ref "U1") (pin "9-10") (pinfunction "SYS_RESET_BTNn_9-10") (pintype "passive+no_connect"))
    )
    (net (code "194") (name "unconnected-(U1-VDD_ADC-Pad9-32)") (class "Default")
      (node (ref "U1") (pin "9-32") (pinfunction "VDD_ADC_9-32") (pintype "passive+no_connect"))
    )
  )
)
